# LM2675_imp.net
KiCad netlist of a schematic drawn in EAGLE
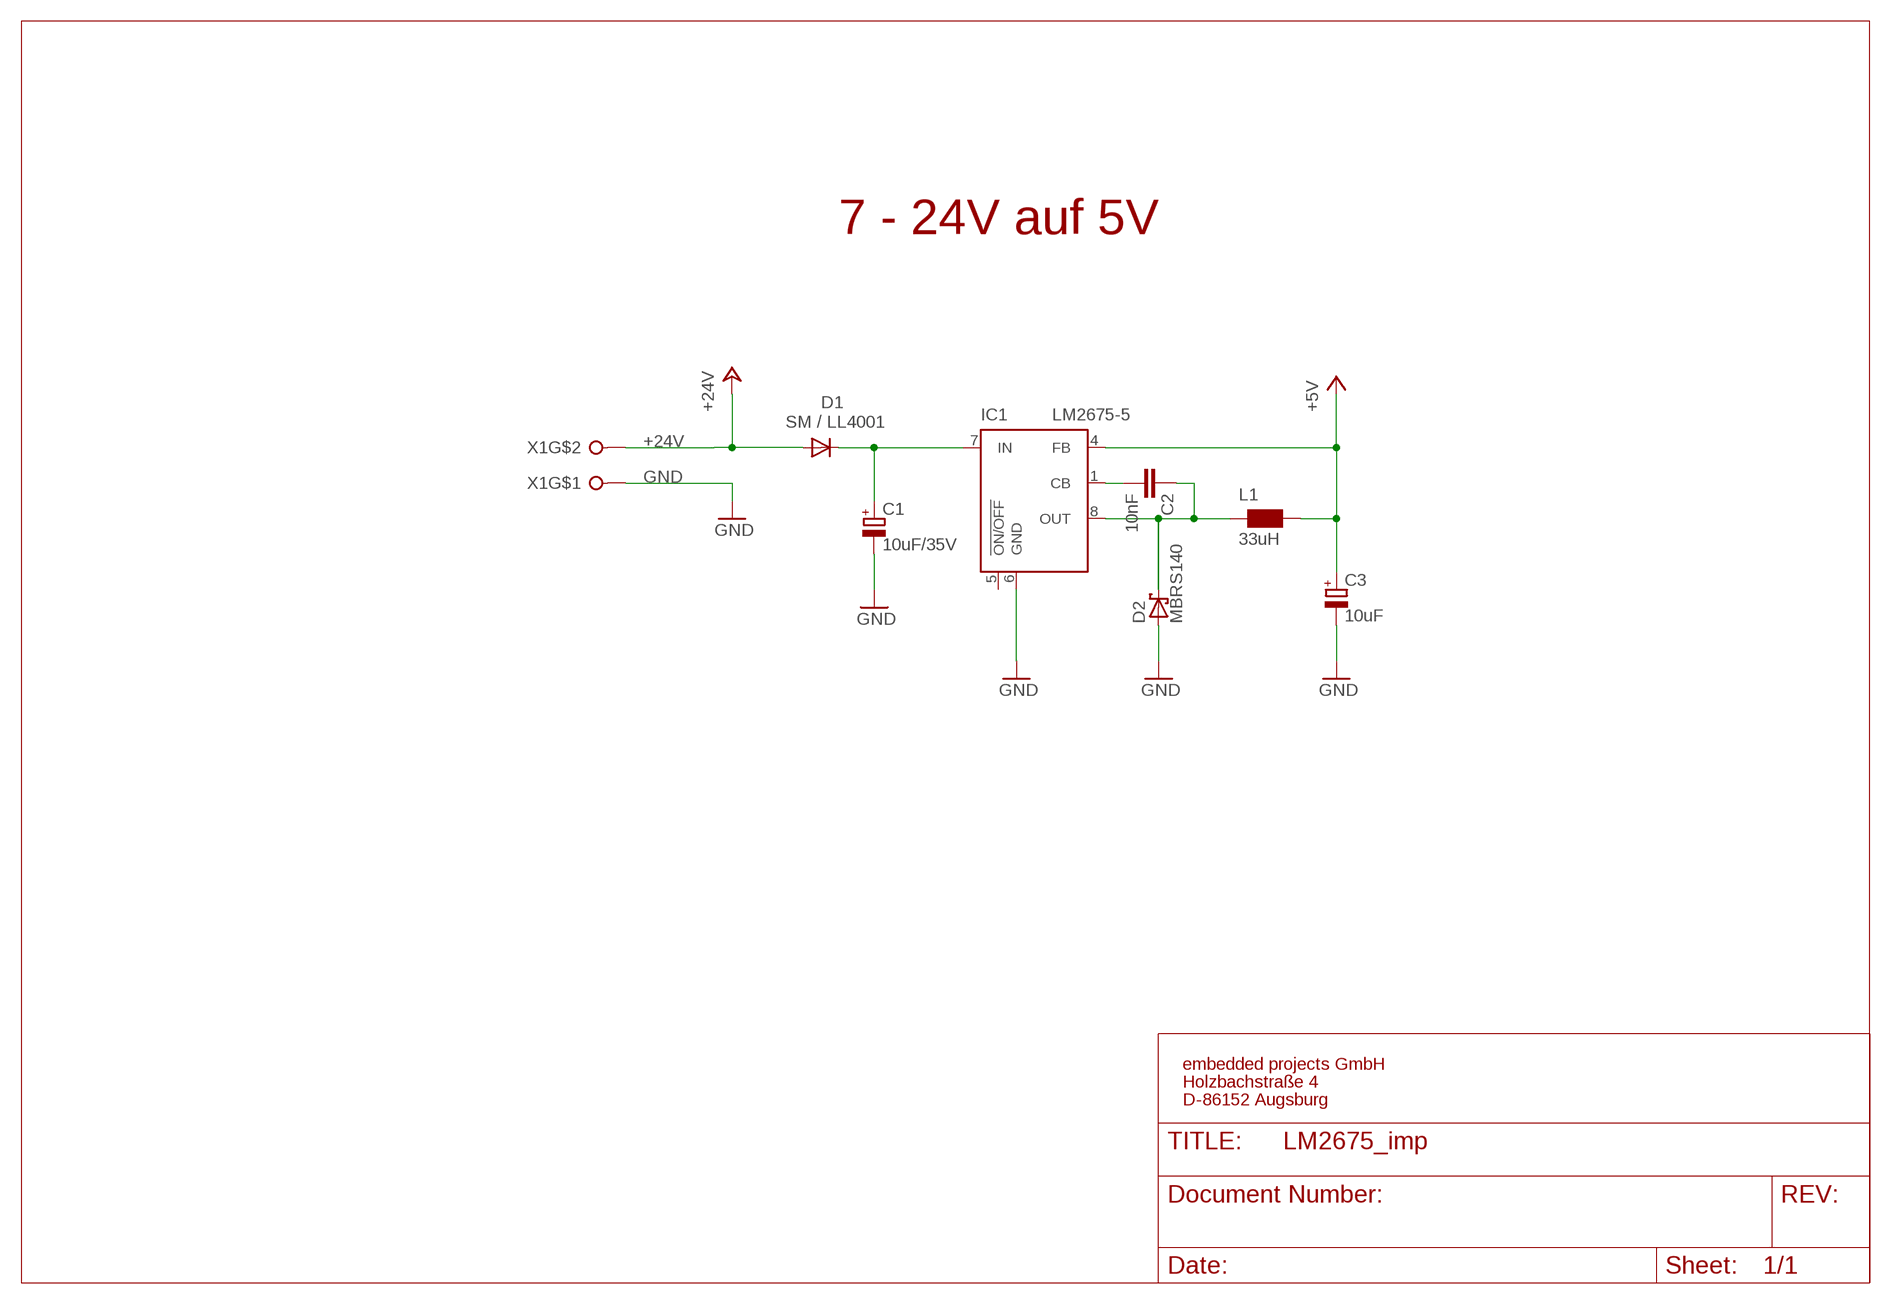
[diagram p0: schematic, sheet 1]

(export (version "E")
  (design (tool "Eeschema 10.0.6"))
  (components
    (comp (ref "C1")
      (value "10uF/35V")
      (footprint "eagle-import:PANASONIC_C")
      (libsource (lib "eagle-import") (part "CPOL-EUC"))
    )
    (comp (ref "C2")
      (value "10nF")
      (footprint "eagle-import:C0805")
      (libsource (lib "eagle-import") (part "C-EUC0805"))
    )
    (comp (ref "C3")
      (value "10uF")
      (footprint "eagle-import:D_7343-31R")
      (libsource (lib "eagle-import") (part "CPOL-EUD/7343-31R"))
    )
    (comp (ref "D1")
      (value "SM / LL4001")
      (footprint "eagle-import:MINIMELF")
      (libsource (lib "eagle-import") (part "DIODE-MINIMELF"))
    )
    (comp (ref "D2")
      (value "MBRS140")
      (footprint "eagle-import:SMB")
      (libsource (lib "eagle-import") (part "MBRS130LT3"))
    )
    (comp (ref "IC1")
      (value "LM2675-5")
      (footprint "eagle-import:SO-8")
      (libsource (lib "eagle-import") (part "LM2675MSO-8"))
    )
    (comp (ref "L1")
      (value "33uH")
      (footprint "eagle-import:WE-PD_S_M")
      (libsource (lib "eagle-import") (part "WE-PD_S/M"))
    )
    (comp (ref "X1")
      (value "CON-WAGO508_W237-02")
      (footprint "eagle-import:W237-132")
      (libsource (lib "eagle-import") (part "CON-WAGO508_W237-02"))
    )
  )
  (nets
    (net (code "1") (name "+5V") (class "Default")
      (node (ref "C3") (pin "+") (pinfunction "+_+") (pintype "passive"))
      (node (ref "IC1") (pin "4") (pinfunction "FB_4") (pintype "input"))
      (node (ref "L1") (pin "1") (pinfunction "2_1") (pintype "passive"))
    )
    (net (code "2") (name "+24V") (class "Default")
      (node (ref "D1") (pin "A") (pinfunction "A_A") (pintype "passive"))
      (node (ref "X1") (pin "2") (pinfunction "KL_2") (pintype "passive"))
    )
    (net (code "3") (name "GND") (class "Default")
      (node (ref "C1") (pin "-") (pinfunction "-_-") (pintype "passive"))
      (node (ref "C3") (pin "-") (pinfunction "-_-") (pintype "passive"))
      (node (ref "D2") (pin "A") (pinfunction "A_A") (pintype "passive"))
      (node (ref "IC1") (pin "6") (pinfunction "GND_6") (pintype "power_in"))
      (node (ref "X1") (pin "1") (pinfunction "KL_1") (pintype "passive"))
    )
    (net (code "4") (name "Net-(IC1-CB)") (class "Default")
      (node (ref "C2") (pin "2") (pinfunction "2_2") (pintype "passive"))
      (node (ref "IC1") (pin "1") (pinfunction "CB_1") (pintype "input"))
    )
    (net (code "5") (name "Net-(IC1-IN)") (class "Default")
      (node (ref "C1") (pin "+") (pinfunction "+_+") (pintype "passive"))
      (node (ref "D1") (pin "C") (pinfunction "C_C") (pintype "passive"))
      (node (ref "IC1") (pin "7") (pinfunction "IN_7") (pintype "input"))
    )
    (net (code "6") (name "Net-(IC1-OUT)") (class "Default")
      (node (ref "C2") (pin "1") (pinfunction "1_1") (pintype "passive"))
      (node (ref "D2") (pin "C") (pinfunction "C_C") (pintype "passive"))
      (node (ref "IC1") (pin "8") (pinfunction "OUT_8") (pintype "passive"))
      (node (ref "L1") (pin "2") (pinfunction "1_2") (pintype "passive"))
    )
    (net (code "7") (name "unconnected-(IC1-~{ON{slash}OFF}-Pad5)") (class "Default")
      (node (ref "IC1") (pin "5") (pinfunction "~{ON/OFF}_5") (pintype "input"))
    )
  )
)
